# Control_Board_V2_RevD.net
KiCad netlist of a schematic drawn in EAGLE
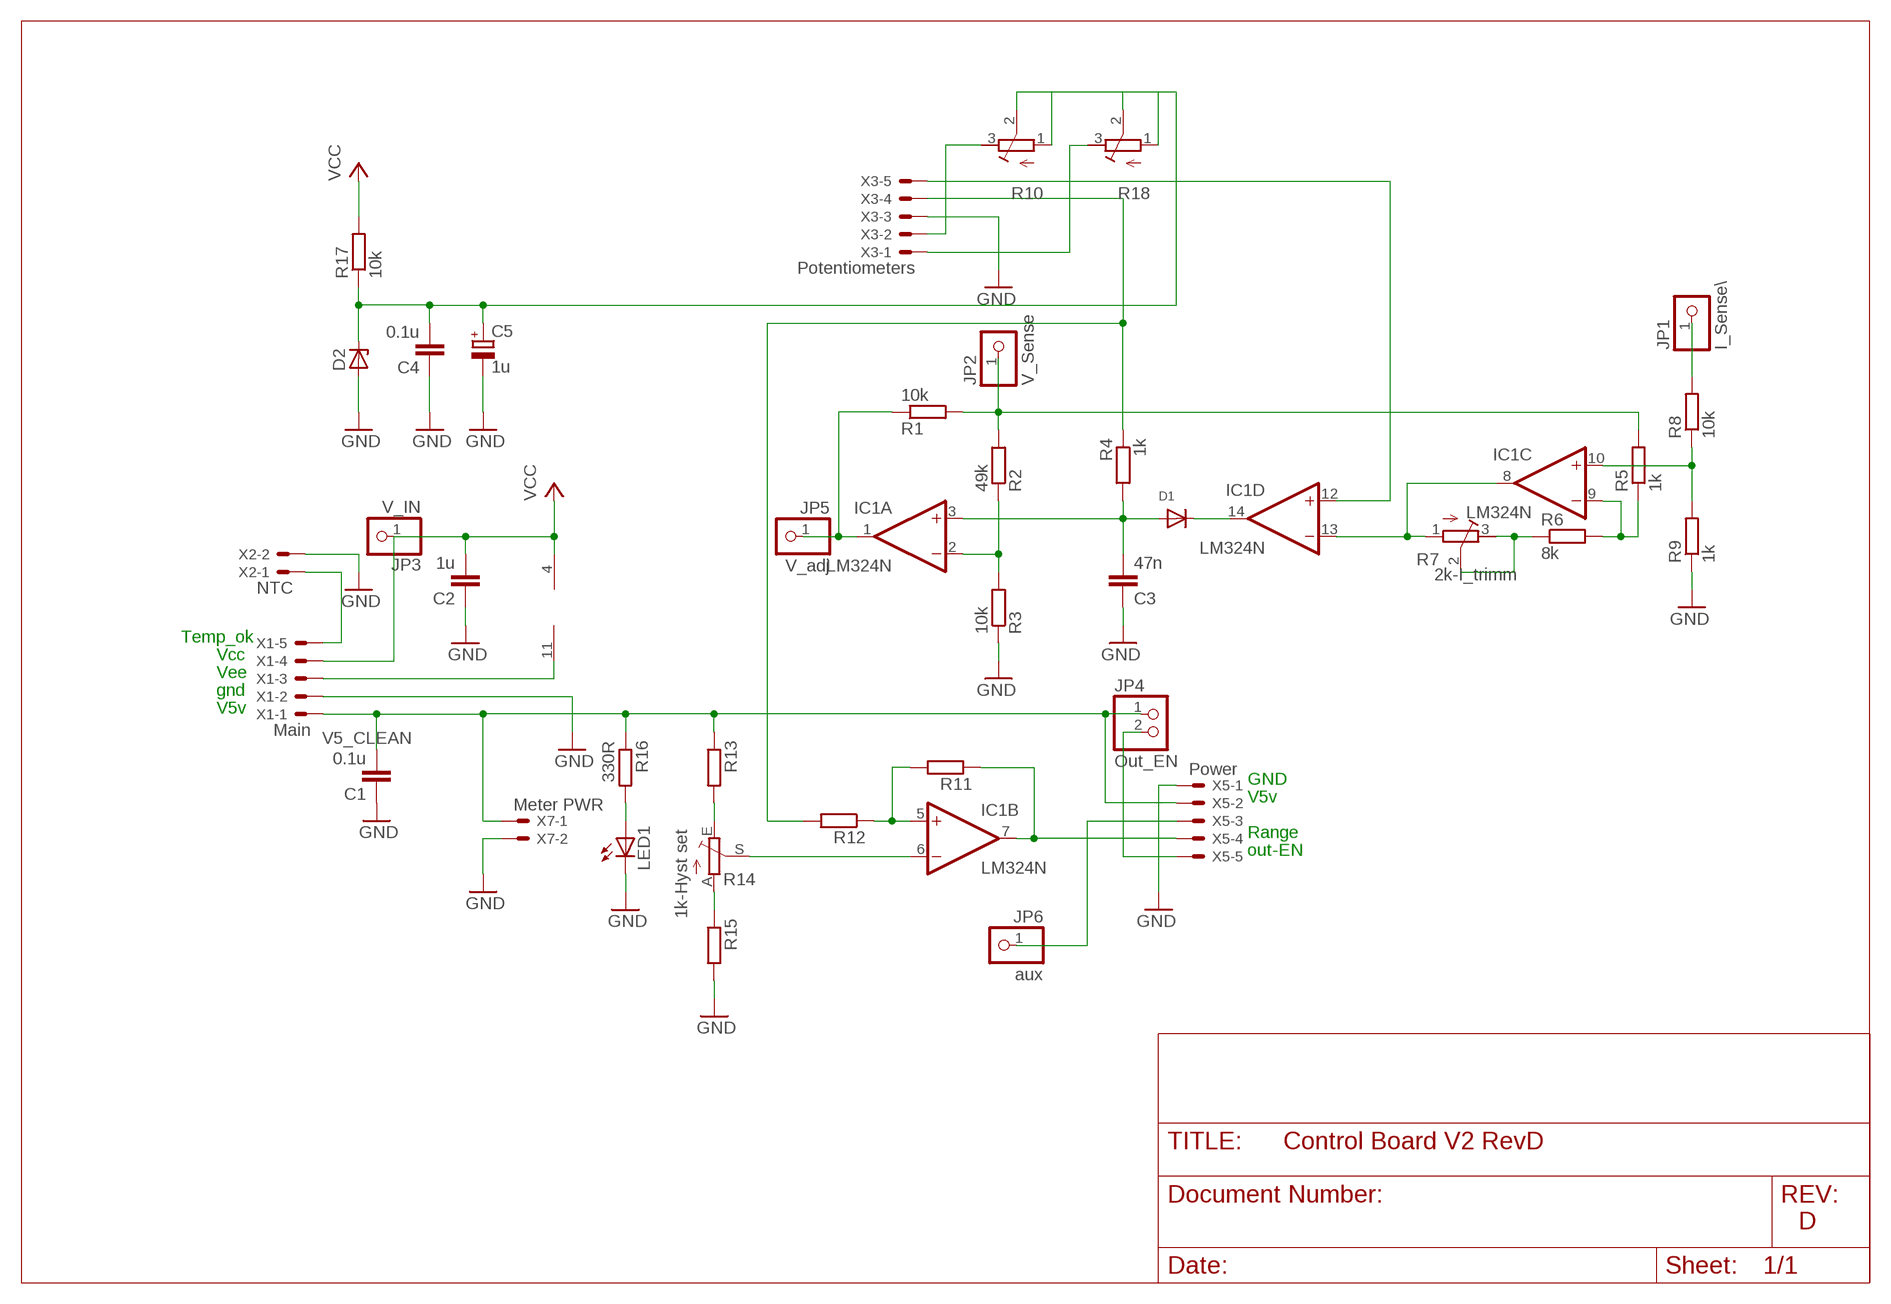
[diagram p0: schematic, sheet 1]

(export (version "E")
  (design (tool "Eeschema 10.0.6"))
  (components
    (comp (ref "C1")
      (value "0.1u")
      (footprint "eagle-import:C050-025X075")
      (libsource (lib "eagle-import") (part "C-EU050-025X075"))
    )
    (comp (ref "C2")
      (value "1u")
      (footprint "eagle-import:C050-025X075")
      (libsource (lib "eagle-import") (part "C-EU050-025X075"))
    )
    (comp (ref "C3")
      (value "47n")
      (footprint "eagle-import:C050-025X075")
      (libsource (lib "eagle-import") (part "C-EU050-025X075"))
    )
    (comp (ref "C4")
      (value "0.1u")
      (footprint "eagle-import:C050-025X075")
      (libsource (lib "eagle-import") (part "C-EU050-025X075"))
    )
    (comp (ref "C5")
      (value "1u")
      (footprint "eagle-import:E5-10,5")
      (libsource (lib "eagle-import") (part "CPOL-EUE5-10.5"))
    )
    (comp (ref "D1")
      (value "DIODEDO-1N4148")
      (footprint "eagle-import:DO-1N4148")
      (libsource (lib "eagle-import") (part "DIODEDO-1N4148"))
    )
    (comp (ref "D2")
      (value "ZENER-DIODEZD-2.5")
      (footprint "eagle-import:ZDIO-2.5")
      (libsource (lib "eagle-import") (part "ZENER-DIODEZD-2.5"))
    )
    (comp (ref "IC1")
      (value "LM324N")
      (footprint "eagle-import:DIL14")
      (libsource (lib "eagle-import") (part "LM324N"))
    )
    (comp (ref "JP1")
      (value "I_Sense\\")
      (footprint "eagle-import:1X01")
      (libsource (lib "eagle-import") (part "PINHD-1X1"))
    )
    (comp (ref "JP2")
      (value "V_Sense")
      (footprint "eagle-import:1X01")
      (libsource (lib "eagle-import") (part "PINHD-1X1"))
    )
    (comp (ref "JP3")
      (value "V_IN")
      (footprint "eagle-import:1X01")
      (libsource (lib "eagle-import") (part "PINHD-1X1"))
    )
    (comp (ref "JP4")
      (value "Out_EN")
      (footprint "eagle-import:1X02")
      (libsource (lib "eagle-import") (part "PINHD-1X2"))
    )
    (comp (ref "JP5")
      (value "V_adj")
      (footprint "eagle-import:1X01")
      (libsource (lib "eagle-import") (part "PINHD-1X1"))
    )
    (comp (ref "JP6")
      (value "aux")
      (footprint "eagle-import:1X01")
      (libsource (lib "eagle-import") (part "PINHD-1X1"))
    )
    (comp (ref "LED1")
      (value "LED3MM")
      (footprint "eagle-import:LED3MM")
      (libsource (lib "eagle-import") (part "LED3MM"))
    )
    (comp (ref "R1")
      (value "10k")
      (footprint "eagle-import:0204_7")
      (libsource (lib "eagle-import") (part "R-EU_0204/7"))
    )
    (comp (ref "R2")
      (value "49k")
      (footprint "eagle-import:0204_7")
      (libsource (lib "eagle-import") (part "R-EU_0204/7"))
    )
    (comp (ref "R3")
      (value "10k")
      (footprint "eagle-import:0204_7")
      (libsource (lib "eagle-import") (part "R-EU_0204/7"))
    )
    (comp (ref "R4")
      (value "1k")
      (footprint "eagle-import:0204_7")
      (libsource (lib "eagle-import") (part "R-EU_0204/7"))
    )
    (comp (ref "R5")
      (value "1k")
      (footprint "eagle-import:0204_5")
      (libsource (lib "eagle-import") (part "R-EU_0204/5"))
    )
    (comp (ref "R6")
      (value "8k")
      (footprint "eagle-import:0204V")
      (libsource (lib "eagle-import") (part "R-EU_0204/2V"))
    )
    (comp (ref "R7")
      (value "2k-I_trimm")
      (footprint "eagle-import:RTRIM64W")
      (libsource (lib "eagle-import") (part "R-TRIMM64W"))
    )
    (comp (ref "R8")
      (value "10k")
      (footprint "eagle-import:0204_7")
      (libsource (lib "eagle-import") (part "R-EU_0204/7"))
    )
    (comp (ref "R9")
      (value "1k")
      (footprint "eagle-import:0204_7")
      (libsource (lib "eagle-import") (part "R-EU_0204/7"))
    )
    (comp (ref "R10")
      (value "R-TRIMM64W")
      (footprint "eagle-import:RTRIM64W")
      (libsource (lib "eagle-import") (part "R-TRIMM64W"))
    )
    (comp (ref "R11")
      (value "R-EU_0204/5")
      (footprint "eagle-import:0204_5")
      (libsource (lib "eagle-import") (part "R-EU_0204/5"))
    )
    (comp (ref "R12")
      (value "R-EU_0204/2V")
      (footprint "eagle-import:0204V")
      (libsource (lib "eagle-import") (part "R-EU_0204/2V"))
    )
    (comp (ref "R13")
      (value "R-EU_0204/2V")
      (footprint "eagle-import:0204V")
      (libsource (lib "eagle-import") (part "R-EU_0204/2V"))
    )
    (comp (ref "R14")
      (value "1k-Hyst set")
      (footprint "eagle-import:B25P")
      (libsource (lib "eagle-import") (part "TRIM_EU-B25P"))
    )
    (comp (ref "R15")
      (value "R-EU_0204/7")
      (footprint "eagle-import:0204_7")
      (libsource (lib "eagle-import") (part "R-EU_0204/7"))
    )
    (comp (ref "R16")
      (value "330R")
      (footprint "eagle-import:0207_2V")
      (libsource (lib "eagle-import") (part "resistor_R-EU_0207/2V"))
    )
    (comp (ref "R17")
      (value "10k")
      (footprint "eagle-import:0204_7")
      (libsource (lib "eagle-import") (part "R-EU_0204/7"))
    )
    (comp (ref "R18")
      (value "R-TRIMM64W")
      (footprint "eagle-import:RTRIM64W")
      (libsource (lib "eagle-import") (part "R-TRIMM64W"))
    )
    (comp (ref "X1")
      (value "Main")
      (footprint "eagle-import:JST-XH-05-PACKAGE-LONG-PAD")
      (libsource (lib "eagle-import") (part "JST-XH-05-PIN-LONG-PAD"))
    )
    (comp (ref "X2")
      (value "NTC")
      (footprint "eagle-import:JST-XH-02-PACKAGE-LONG-PAD")
      (libsource (lib "eagle-import") (part "JST-XH-02-PIN-LONG-PAD"))
    )
    (comp (ref "X3")
      (value "Potentiometers")
      (footprint "eagle-import:JST-XH-05-PACKAGE-LONG-PAD")
      (libsource (lib "eagle-import") (part "JST-XH-05-PIN-LONG-PAD"))
    )
    (comp (ref "X5")
      (value "Power")
      (footprint "eagle-import:JST-XH-05-PACKAGE-LONG-PAD")
      (libsource (lib "eagle-import") (part "JST-XH-05-PIN-LONG-PAD"))
    )
    (comp (ref "X7")
      (value "Meter PWR")
      (footprint "eagle-import:JST-XH-02-PACKAGE-LONG-PAD")
      (libsource (lib "eagle-import") (part "JST-XH-02-PIN-LONG-PAD"))
    )
  )
  (nets
    (net (code "1") (name "/V5_CLEAN") (class "Default")
      (node (ref "C1") (pin "2") (pinfunction "2_2") (pintype "passive"))
      (node (ref "JP4") (pin "1") (pinfunction "1_1") (pintype "passive"))
      (node (ref "R13") (pin "1") (pinfunction "1_1") (pintype "passive"))
      (node (ref "R16") (pin "1") (pinfunction "1_1") (pintype "passive"))
      (node (ref "X1") (pin "1") (pinfunction "S_1") (pintype "passive"))
      (node (ref "X5") (pin "2") (pinfunction "S_2") (pintype "passive"))
      (node (ref "X7") (pin "1") (pinfunction "S_1") (pintype "passive"))
    )
    (net (code "2") (name "GND") (class "Default")
      (node (ref "C1") (pin "1") (pinfunction "1_1") (pintype "passive"))
      (node (ref "C2") (pin "1") (pinfunction "1_1") (pintype "passive"))
      (node (ref "C3") (pin "1") (pinfunction "1_1") (pintype "passive"))
      (node (ref "C4") (pin "1") (pinfunction "1_1") (pintype "passive"))
      (node (ref "C5") (pin "-") (pinfunction "-_-") (pintype "passive"))
      (node (ref "D2") (pin "A") (pinfunction "A_A") (pintype "passive"))
      (node (ref "LED1") (pin "K") (pinfunction "C_K") (pintype "passive"))
      (node (ref "R15") (pin "2") (pinfunction "2_2") (pintype "passive"))
      (node (ref "R3") (pin "1") (pinfunction "1_1") (pintype "passive"))
      (node (ref "R9") (pin "1") (pinfunction "1_1") (pintype "passive"))
      (node (ref "X1") (pin "2") (pinfunction "S_2") (pintype "passive"))
      (node (ref "X2") (pin "2") (pinfunction "S_2") (pintype "passive"))
      (node (ref "X3") (pin "3") (pinfunction "S_3") (pintype "passive"))
      (node (ref "X5") (pin "1") (pinfunction "S_1") (pintype "passive"))
      (node (ref "X7") (pin "2") (pinfunction "S_2") (pintype "passive"))
    )
    (net (code "3") (name "Net-(IC1A-+IN)") (class "Default")
      (node (ref "C3") (pin "2") (pinfunction "2_2") (pintype "passive"))
      (node (ref "D1") (pin "A") (pinfunction "A_A") (pintype "passive"))
      (node (ref "IC1") (pin "3") (pinfunction "+IN_3") (pintype "input"))
      (node (ref "R4") (pin "2") (pinfunction "2_2") (pintype "passive"))
    )
    (net (code "4") (name "Net-(IC1A--IN)") (class "Default")
      (node (ref "IC1") (pin "2") (pinfunction "-IN_2") (pintype "input"))
      (node (ref "R2") (pin "1") (pinfunction "1_1") (pintype "passive"))
      (node (ref "R3") (pin "2") (pinfunction "2_2") (pintype "passive"))
    )
    (net (code "5") (name "Net-(IC1A-OUT)") (class "Default")
      (node (ref "IC1") (pin "1") (pinfunction "OUT_1") (pintype "output"))
      (node (ref "JP5") (pin "1") (pinfunction "1_1") (pintype "passive"))
      (node (ref "R1") (pin "1") (pinfunction "1_1") (pintype "passive"))
    )
    (net (code "6") (name "Net-(IC1B-+IN)") (class "Default")
      (node (ref "IC1") (pin "5") (pinfunction "+IN_5") (pintype "input"))
      (node (ref "R11") (pin "2") (pinfunction "2_2") (pintype "passive"))
      (node (ref "R12") (pin "1") (pinfunction "1_1") (pintype "passive"))
    )
    (net (code "7") (name "Net-(IC1B--IN)") (class "Default")
      (node (ref "IC1") (pin "6") (pinfunction "-IN_6") (pintype "input"))
      (node (ref "R14") (pin "S") (pinfunction "S_S") (pintype "passive"))
    )
    (net (code "8") (name "Net-(IC1B-OUT)") (class "Default")
      (node (ref "IC1") (pin "7") (pinfunction "OUT_7") (pintype "output"))
      (node (ref "R11") (pin "1") (pinfunction "1_1") (pintype "passive"))
      (node (ref "X5") (pin "4") (pinfunction "S_4") (pintype "passive"))
    )
    (net (code "9") (name "Net-(IC1C-+IN)") (class "Default")
      (node (ref "IC1") (pin "10") (pinfunction "+IN_10") (pintype "input"))
      (node (ref "R8") (pin "1") (pinfunction "1_1") (pintype "passive"))
      (node (ref "R9") (pin "2") (pinfunction "2_2") (pintype "passive"))
    )
    (net (code "10") (name "Net-(IC1C--IN)") (class "Default")
      (node (ref "IC1") (pin "9") (pinfunction "-IN_9") (pintype "input"))
      (node (ref "R5") (pin "1") (pinfunction "1_1") (pintype "passive"))
      (node (ref "R6") (pin "2") (pinfunction "2_2") (pintype "passive"))
    )
    (net (code "11") (name "Net-(IC1C-OUT)") (class "Default")
      (node (ref "IC1") (pin "13") (pinfunction "-IN_13") (pintype "input"))
      (node (ref "IC1") (pin "8") (pinfunction "OUT_8") (pintype "output"))
      (node (ref "R7") (pin "1") (pinfunction "A_1") (pintype "passive"))
    )
    (net (code "12") (name "Net-(IC1D-+IN)") (class "Default")
      (node (ref "IC1") (pin "12") (pinfunction "+IN_12") (pintype "input"))
      (node (ref "X3") (pin "5") (pinfunction "S_5") (pintype "passive"))
    )
    (net (code "13") (name "Net-(IC1D-OUT)") (class "Default")
      (node (ref "D1") (pin "C") (pinfunction "C_C") (pintype "passive"))
      (node (ref "IC1") (pin "14") (pinfunction "OUT_14") (pintype "output"))
    )
    (net (code "14") (name "Net-(IC1E-V-)") (class "Default")
      (node (ref "IC1") (pin "11") (pinfunction "V-_11") (pintype "power_in"))
      (node (ref "X1") (pin "3") (pinfunction "S_3") (pintype "passive"))
    )
    (net (code "15") (name "Net-(JP1-Pad1)") (class "Default")
      (node (ref "JP1") (pin "1") (pinfunction "1_1") (pintype "passive"))
      (node (ref "R8") (pin "2") (pinfunction "2_2") (pintype "passive"))
    )
    (net (code "16") (name "Net-(JP2-Pad1)") (class "Default")
      (node (ref "JP2") (pin "1") (pinfunction "1_1") (pintype "passive"))
      (node (ref "R1") (pin "2") (pinfunction "2_2") (pintype "passive"))
      (node (ref "R2") (pin "2") (pinfunction "2_2") (pintype "passive"))
      (node (ref "R5") (pin "2") (pinfunction "2_2") (pintype "passive"))
    )
    (net (code "17") (name "Net-(LED1-PadA)") (class "Default")
      (node (ref "LED1") (pin "A") (pinfunction "A_A") (pintype "passive"))
      (node (ref "R16") (pin "2") (pinfunction "2_2") (pintype "passive"))
    )
    (net (code "18") (name "Net-(R7-E)") (class "Default")
      (node (ref "R6") (pin "1") (pinfunction "1_1") (pintype "passive"))
      (node (ref "R7") (pin "2") (pinfunction "S_2") (pintype "passive"))
      (node (ref "R7") (pin "3") (pinfunction "E_3") (pintype "passive"))
    )
    (net (code "19") (name "Net-(R10-A)") (class "Default")
      (node (ref "C4") (pin "2") (pinfunction "2_2") (pintype "passive"))
      (node (ref "C5") (pin "+") (pinfunction "+_+") (pintype "passive"))
      (node (ref "D2") (pin "C") (pinfunction "C_C") (pintype "passive"))
      (node (ref "R10") (pin "1") (pinfunction "A_1") (pintype "passive"))
      (node (ref "R10") (pin "2") (pinfunction "S_2") (pintype "passive"))
      (node (ref "R17") (pin "1") (pinfunction "1_1") (pintype "passive"))
      (node (ref "R18") (pin "1") (pinfunction "A_1") (pintype "passive"))
      (node (ref "R18") (pin "2") (pinfunction "S_2") (pintype "passive"))
    )
    (net (code "20") (name "Net-(R10-E)") (class "Default")
      (node (ref "R10") (pin "3") (pinfunction "E_3") (pintype "passive"))
      (node (ref "X3") (pin "2") (pinfunction "S_2") (pintype "passive"))
    )
    (net (code "21") (name "Net-(R13-Pad2)") (class "Default")
      (node (ref "R13") (pin "2") (pinfunction "2_2") (pintype "passive"))
      (node (ref "R14") (pin "E") (pinfunction "E_E") (pintype "passive"))
    )
    (net (code "22") (name "Net-(R14-PadA)") (class "Default")
      (node (ref "R14") (pin "A") (pinfunction "A_A") (pintype "passive"))
      (node (ref "R15") (pin "1") (pinfunction "1_1") (pintype "passive"))
    )
    (net (code "23") (name "Net-(R18-E)") (class "Default")
      (node (ref "R18") (pin "3") (pinfunction "E_3") (pintype "passive"))
      (node (ref "X3") (pin "1") (pinfunction "S_1") (pintype "passive"))
    )
    (net (code "24") (name "Net-(X1E-S)") (class "Default")
      (node (ref "X1") (pin "5") (pinfunction "S_5") (pintype "passive"))
      (node (ref "X2") (pin "1") (pinfunction "S_1") (pintype "passive"))
    )
    (net (code "25") (name "Net-(X3D-S)") (class "Default")
      (node (ref "R12") (pin "2") (pinfunction "2_2") (pintype "passive"))
      (node (ref "R4") (pin "1") (pinfunction "1_1") (pintype "passive"))
      (node (ref "X3") (pin "4") (pinfunction "S_4") (pintype "passive"))
    )
    (net (code "26") (name "Net-(X5C-S)") (class "Default")
      (node (ref "JP6") (pin "1") (pinfunction "1_1") (pintype "passive"))
      (node (ref "X5") (pin "3") (pinfunction "S_3") (pintype "passive"))
    )
    (net (code "27") (name "Net-(X5E-S)") (class "Default")
      (node (ref "JP4") (pin "2") (pinfunction "2_2") (pintype "passive"))
      (node (ref "X5") (pin "5") (pinfunction "S_5") (pintype "passive"))
    )
    (net (code "28") (name "VCC") (class "Default")
      (node (ref "C2") (pin "2") (pinfunction "2_2") (pintype "passive"))
      (node (ref "IC1") (pin "4") (pinfunction "V+_4") (pintype "power_in"))
      (node (ref "JP3") (pin "1") (pinfunction "1_1") (pintype "passive"))
      (node (ref "R17") (pin "2") (pinfunction "2_2") (pintype "passive"))
      (node (ref "X1") (pin "4") (pinfunction "S_4") (pintype "passive"))
    )
  )
)
